# Mosfets.net
KiCad netlist of a schematic drawn in Altium Designer
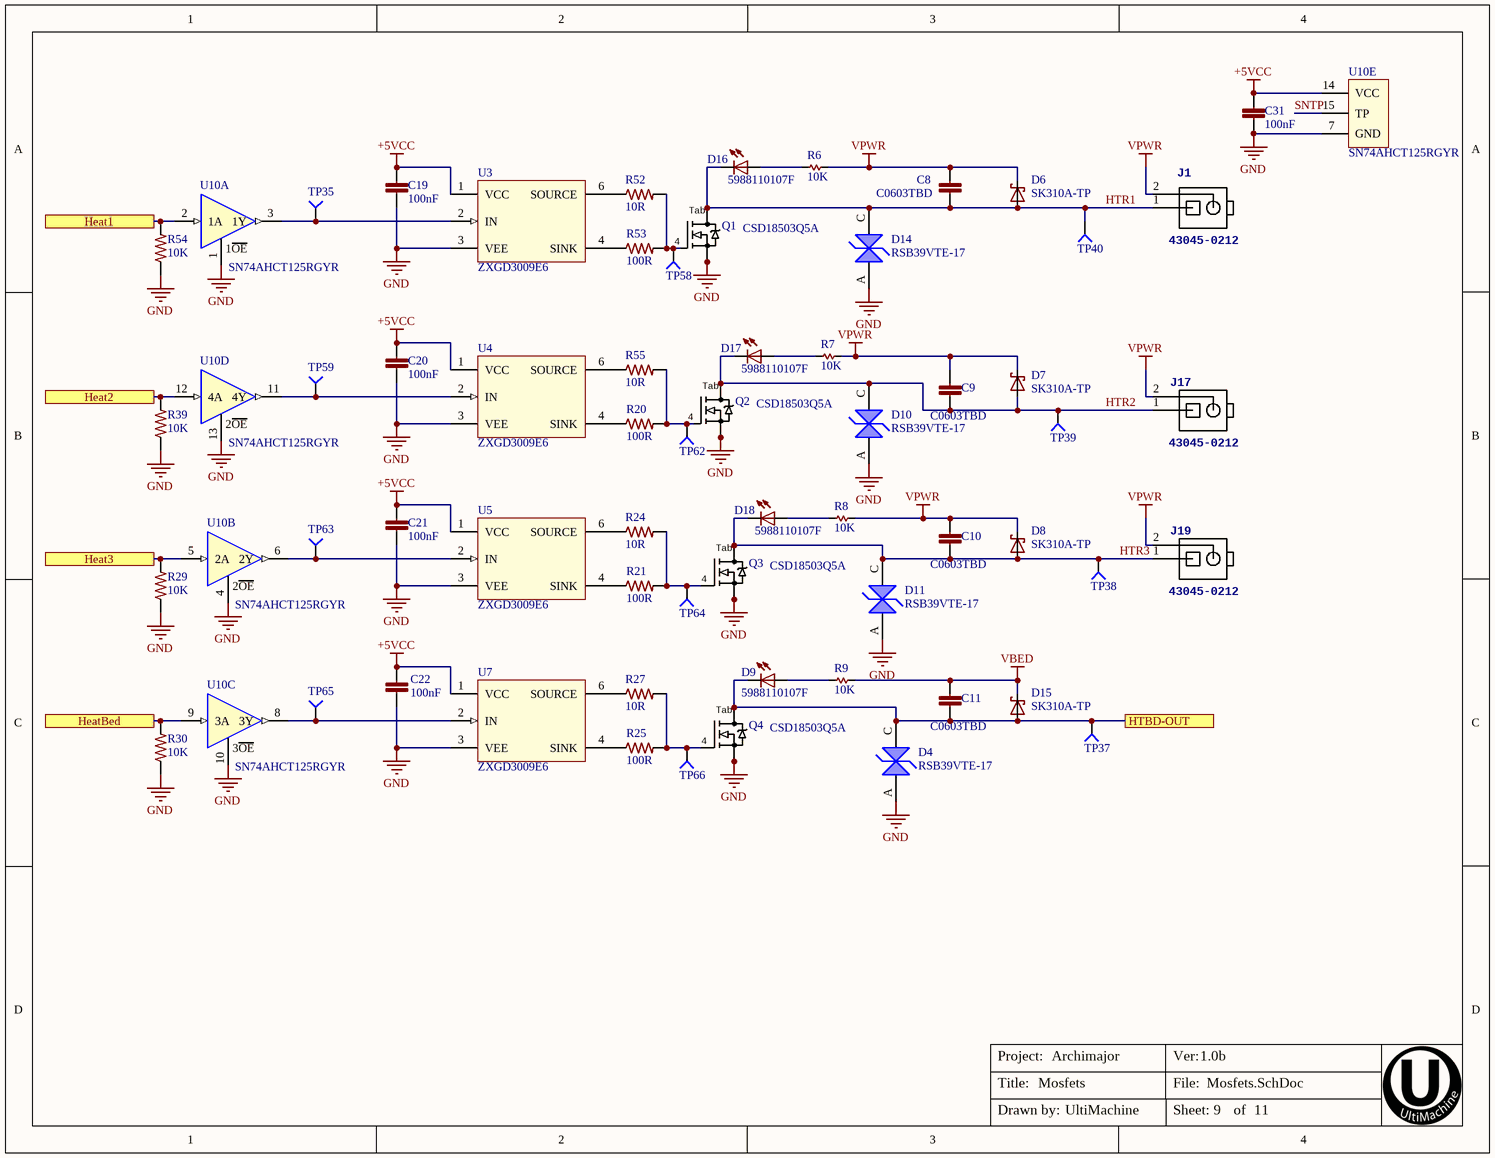
[diagram p0: Mosfets.SchDoc]

(export (version "E")
  (design (tool "Eeschema 10.0.6"))
  (components
    (comp (ref "C8")
      (value "C0603TBD")
      (footprint "C0603")
      (description "Capacitor Non Polarized")
      (fields (field (name "PART") "DNI-C0603TBD"))
      (libsource (lib "3Delight") (part "C0603TBD"))
    )
    (comp (ref "C9")
      (value "C0603TBD")
      (footprint "C0603")
      (description "Capacitor Non Polarized")
      (fields (field (name "PART") "DNI-C0603TBD"))
      (libsource (lib "3Delight") (part "C0603TBD"))
    )
    (comp (ref "C10")
      (value "C0603TBD")
      (footprint "C0603")
      (description "Capacitor Non Polarized")
      (fields (field (name "PART") "DNI-C0603TBD"))
      (libsource (lib "3Delight") (part "C0603TBD"))
    )
    (comp (ref "C11")
      (value "C0603TBD")
      (footprint "C0603")
      (description "Capacitor Non Polarized")
      (fields (field (name "PART") "DNI-C0603TBD"))
      (libsource (lib "3Delight") (part "C0603TBD"))
    )
    (comp (ref "C19")
      (value "100nF")
      (footprint "C0402")
      (description "CAP CER 0402 100nF 16V 10% X7R")
      (fields (field (name "MANUFACTURER") "Murata") (field (name "PART") "GRM155R71C104KA88D"))
      (libsource (lib "3Delight") (part "GRM155R71C104KA88D"))
    )
    (comp (ref "C20")
      (value "100nF")
      (footprint "C0402")
      (description "CAP CER 0402 100nF 16V 10% X7R")
      (fields (field (name "MANUFACTURER") "Murata") (field (name "PART") "GRM155R71C104KA88D"))
      (libsource (lib "3Delight") (part "GRM155R71C104KA88D"))
    )
    (comp (ref "C21")
      (value "100nF")
      (footprint "C0402")
      (description "CAP CER 0402 100nF 16V 10% X7R")
      (fields (field (name "MANUFACTURER") "Murata") (field (name "PART") "GRM155R71C104KA88D"))
      (libsource (lib "3Delight") (part "GRM155R71C104KA88D"))
    )
    (comp (ref "C22")
      (value "100nF")
      (footprint "C0402")
      (description "CAP CER 0402 100nF 16V 10% X7R")
      (fields (field (name "MANUFACTURER") "Murata") (field (name "PART") "GRM155R71C104KA88D"))
      (libsource (lib "") (part "GRM155R71C104KA88D_1"))
    )
    (comp (ref "C31")
      (value "100nF")
      (footprint "C0402")
      (description "CAP CER 0402 100nF 16V 10% X7R")
      (fields (field (name "MANUFACTURER") "Murata") (field (name "PART") "GRM155R71C104KA88D"))
      (libsource (lib "3Delight") (part "GRM155R71C104KA88D"))
    )
    (comp (ref "D4")
      (value "RSB39VTE-17")
      (footprint "SOD323-R")
      (description "DIODE TVS")
      (fields (field (name "MANUFACTURER") "Rohm") (field (name "TOLERANCE") "-NA-"))
      (libsource (lib "3Delight") (part "RSB39VTE-17"))
    )
    (comp (ref "D6")
      (value "SK310A-TP")
      (footprint "SMA-SM")
      (description "DIODE Schottky 3A SMA")
      (fields (field (name "MANUFACTURER") "MCC") (field (name "PART") "SK310A"))
      (libsource (lib "Archim_0.4") (part "SK310A"))
    )
    (comp (ref "D7")
      (value "SK310A-TP")
      (footprint "SMA-SM")
      (description "DIODE Schottky 3A SMA")
      (fields (field (name "MANUFACTURER") "MCC") (field (name "PART") "SK310A"))
      (libsource (lib "Archim_0.4") (part "SK310A"))
    )
    (comp (ref "D8")
      (value "SK310A-TP")
      (footprint "SMA-SM")
      (description "DIODE Schottky 3A SMA")
      (fields (field (name "MANUFACTURER") "MCC") (field (name "PART") "SK310A"))
      (libsource (lib "Archim_0.4") (part "SK310A"))
    )
    (comp (ref "D9")
      (value "Red")
      (footprint "LED2012120")
      (description "LED 0805 Red")
      (fields
        (field (name "MANUFACTURER") "Dialight")
        (field (name "PART") "5988110107F")
        (field (name "TOLERANCE") "-NA-")
      )
      (libsource (lib "3Delight") (part "5988110107F"))
    )
    (comp (ref "D10")
      (value "RSB39VTE-17")
      (footprint "SOD323-R")
      (description "DIODE TVS")
      (fields (field (name "MANUFACTURER") "Rohm") (field (name "TOLERANCE") "-NA-"))
      (libsource (lib "3Delight") (part "RSB39VTE-17"))
    )
    (comp (ref "D11")
      (value "RSB39VTE-17")
      (footprint "SOD323-R")
      (description "DIODE TVS")
      (fields (field (name "MANUFACTURER") "Rohm") (field (name "TOLERANCE") "-NA-"))
      (libsource (lib "3Delight") (part "RSB39VTE-17"))
    )
    (comp (ref "D14")
      (value "RSB39VTE-17")
      (footprint "SOD323-R")
      (description "DIODE TVS")
      (fields (field (name "MANUFACTURER") "Rohm") (field (name "TOLERANCE") "-NA-"))
      (libsource (lib "3Delight") (part "RSB39VTE-17"))
    )
    (comp (ref "D15")
      (value "SK310A-TP")
      (footprint "SMA-SM")
      (description "DIODE Schottky 3A SMA")
      (fields (field (name "MANUFACTURER") "MCC") (field (name "PART") "SK310A"))
      (libsource (lib "Archim_0.4") (part "SK310A"))
    )
    (comp (ref "D16")
      (value "Red")
      (footprint "LED2012120")
      (description "LED 0805 Red")
      (fields
        (field (name "MANUFACTURER") "Dialight")
        (field (name "PART") "5988110107F")
        (field (name "TOLERANCE") "-NA-")
      )
      (libsource (lib "3Delight") (part "5988110107F"))
    )
    (comp (ref "D17")
      (value "Red")
      (footprint "LED2012120")
      (description "LED 0805 Red")
      (fields
        (field (name "MANUFACTURER") "Dialight")
        (field (name "PART") "5988110107F")
        (field (name "TOLERANCE") "-NA-")
      )
      (libsource (lib "3Delight") (part "5988110107F"))
    )
    (comp (ref "D18")
      (value "Red")
      (footprint "LED2012120")
      (description "LED 0805 Red")
      (fields
        (field (name "MANUFACTURER") "Dialight")
        (field (name "PART") "5988110107F")
        (field (name "TOLERANCE") "-NA-")
      )
      (libsource (lib "3Delight") (part "5988110107F"))
    )
    (comp (ref "J1")
      (value "43045-0212")
      (footprint "43045-0212")
      (description "Conn - 3mm Pitch Fixed")
      (fields (field (name "MANUFACTURER") "Molex"))
      (libsource (lib "Connectors") (part "Micro-Fit THT 2pos 3mm"))
    )
    (comp (ref "J17")
      (value "43045-0212")
      (footprint "43045-0212")
      (description "Conn - 3mm Pitch Fixed")
      (fields (field (name "MANUFACTURER") "Molex"))
      (libsource (lib "Connectors") (part "Micro-Fit THT 2pos 3mm"))
    )
    (comp (ref "J19")
      (value "43045-0212")
      (footprint "43045-0212")
      (description "Conn - 3mm Pitch Fixed")
      (fields (field (name "MANUFACTURER") "Molex"))
      (libsource (lib "Connectors") (part "Micro-Fit THT 2pos 3mm"))
    )
    (comp (ref "Q1")
      (value "CSD18503Q5A")
      (footprint "SOT669_Universal")
      (description "MOSFET N-CH 40V 100A 8VSON")
      (fields (field (name "MANUFACTURER") "TI"))
      (libsource (lib "Transistors") (part "CSD18503Q5A"))
    )
    (comp (ref "Q2")
      (value "CSD18503Q5A")
      (footprint "SOT669_Universal")
      (description "MOSFET N-CH 40V 100A 8VSON")
      (fields (field (name "MANUFACTURER") "TI"))
      (libsource (lib "Transistors") (part "CSD18503Q5A"))
    )
    (comp (ref "Q3")
      (value "CSD18503Q5A")
      (footprint "SOT669_Universal")
      (description "MOSFET N-CH 40V 100A 8VSON")
      (fields (field (name "MANUFACTURER") "TI"))
      (libsource (lib "Transistors") (part "CSD18503Q5A"))
    )
    (comp (ref "Q4")
      (value "CSD18503Q5A")
      (footprint "SOT669_Universal")
      (description "MOSFET N-CH 40V 100A 8VSON")
      (fields (field (name "MANUFACTURER") "TI"))
      (libsource (lib "Transistors") (part "CSD18503Q5A"))
    )
    (comp (ref "R6")
      (value "10K")
      (footprint "R0402")
      (description "RES SMD 10K OHM 1% 1/16W 0402")
      (fields (field (name "MANUFACTURER") "Yageo") (field (name "PART") "RC0402FR-0710KP"))
      (libsource (lib "Resistors") (part "10k 1% 0402"))
    )
    (comp (ref "R7")
      (value "10K")
      (footprint "R0402")
      (description "RES SMD 10K OHM 1% 1/16W 0402")
      (fields (field (name "MANUFACTURER") "Yageo") (field (name "PART") "RC0402FR-0710KP"))
      (libsource (lib "Resistors") (part "10k 1% 0402"))
    )
    (comp (ref "R8")
      (value "10K")
      (footprint "R0402")
      (description "RES SMD 10K OHM 1% 1/16W 0402")
      (fields (field (name "MANUFACTURER") "Yageo") (field (name "PART") "RC0402FR-0710KP"))
      (libsource (lib "Resistors") (part "10k 1% 0402"))
    )
    (comp (ref "R9")
      (value "10K")
      (footprint "R0402")
      (description "RES SMD 10K OHM 1% 1/16W 0402")
      (fields (field (name "MANUFACTURER") "Yageo") (field (name "PART") "RC0402FR-0710KP"))
      (libsource (lib "Resistors") (part "10k 1% 0402"))
    )
    (comp (ref "R20")
      (value "100R")
      (footprint "R0402")
      (description "RES SMD 100 OHM 1% 1/16W 0402")
      (fields (field (name "MANUFACTURER") "Yageo") (field (name "PART") "RC0402FR-07100RL"))
      (libsource (lib "Archim") (part "RES 100R 0402 1%"))
    )
    (comp (ref "R21")
      (value "100R")
      (footprint "R0402")
      (description "RES SMD 100 OHM 1% 1/16W 0402")
      (fields (field (name "MANUFACTURER") "Yageo") (field (name "PART") "RC0402FR-07100RL"))
      (libsource (lib "Archim") (part "RES 100R 0402 1%"))
    )
    (comp (ref "R24")
      (value "10R")
      (footprint "R0402")
      (description "RES SMD 10 OHM 1% 1/16W 0402")
      (fields (field (name "MANUFACTURER") "Yageo") (field (name "PART") "RC0402FR-0710RL"))
      (libsource (lib "3Delight") (part "RC0402FR-0710RL"))
    )
    (comp (ref "R25")
      (value "100R")
      (footprint "R0402")
      (description "RES SMD 100 OHM 1% 1/16W 0402")
      (fields (field (name "MANUFACTURER") "Yageo") (field (name "PART") "RC0402FR-07100RL"))
      (libsource (lib "Archim") (part "RES 100R 0402 1%"))
    )
    (comp (ref "R27")
      (value "10R")
      (footprint "R0402")
      (description "RES SMD 10 OHM 1% 1/16W 0402")
      (fields (field (name "MANUFACTURER") "Yageo") (field (name "PART") "RC0402FR-0710RL"))
      (libsource (lib "3Delight") (part "RC0402FR-0710RL"))
    )
    (comp (ref "R29")
      (value "10K")
      (footprint "R0402")
      (description "RES SMD 10K OHM 1% 1/16W 0402")
      (fields (field (name "MANUFACTURER") "Yageo") (field (name "PART") "RC0402FR-0710KP"))
      (libsource (lib "3Delight") (part "RC0402FR-0710KP"))
    )
    (comp (ref "R30")
      (value "10K")
      (footprint "R0402")
      (description "RES SMD 10K OHM 1% 1/16W 0402")
      (fields (field (name "MANUFACTURER") "Yageo") (field (name "PART") "RC0402FR-0710KP"))
      (libsource (lib "3Delight") (part "RC0402FR-0710KP"))
    )
    (comp (ref "R39")
      (value "10K")
      (footprint "R0402")
      (description "RES SMD 10K OHM 1% 1/16W 0402")
      (fields (field (name "MANUFACTURER") "Yageo") (field (name "PART") "RC0402FR-0710KP"))
      (libsource (lib "3Delight") (part "RC0402FR-0710KP"))
    )
    (comp (ref "R52")
      (value "10R")
      (footprint "R0402")
      (description "RES SMD 10 OHM 1% 1/16W 0402")
      (fields (field (name "MANUFACTURER") "Yageo") (field (name "PART") "RC0402FR-0710RL"))
      (libsource (lib "3Delight") (part "RC0402FR-0710RL"))
    )
    (comp (ref "R53")
      (value "100R")
      (footprint "R0402")
      (description "RES SMD 100 OHM 1% 1/16W 0402")
      (fields (field (name "MANUFACTURER") "Yageo") (field (name "PART") "RC0402FR-07100RL"))
      (libsource (lib "Archim") (part "RES 100R 0402 1%"))
    )
    (comp (ref "R54")
      (value "10K")
      (footprint "R0402")
      (description "RES SMD 10K OHM 1% 1/16W 0402")
      (fields (field (name "MANUFACTURER") "Yageo") (field (name "PART") "RC0402FR-0710KP"))
      (libsource (lib "3Delight") (part "RC0402FR-0710KP"))
    )
    (comp (ref "R55")
      (value "10R")
      (footprint "R0402")
      (description "RES SMD 10 OHM 1% 1/16W 0402")
      (fields (field (name "MANUFACTURER") "Yageo") (field (name "PART") "RC0402FR-0710RL"))
      (libsource (lib "3Delight") (part "RC0402FR-0710RL"))
    )
    (comp (ref "TP35")
      (value "TP4")
      (footprint "TP-2")
      (description "Socket")
      (fields (field (name "PART") "NOTAPART-Testpoint"))
      (libsource (lib "Archim") (part "Socket"))
    )
    (comp (ref "TP37")
      (value "TP4")
      (footprint "TP-2")
      (description "Socket")
      (fields (field (name "PART") "NOTAPART-Testpoint"))
      (libsource (lib "Archim") (part "Socket"))
    )
    (comp (ref "TP38")
      (value "TP4")
      (footprint "TP-2")
      (description "Socket")
      (fields (field (name "PART") "NOTAPART-Testpoint"))
      (libsource (lib "Archim") (part "Socket"))
    )
    (comp (ref "TP39")
      (value "TP4")
      (footprint "TP-2")
      (description "Socket")
      (fields (field (name "PART") "NOTAPART-Testpoint"))
      (libsource (lib "Archim") (part "Socket"))
    )
    (comp (ref "TP40")
      (value "TP4")
      (footprint "TP-2")
      (description "Socket")
      (fields (field (name "PART") "NOTAPART-Testpoint"))
      (libsource (lib "Archim") (part "Socket"))
    )
    (comp (ref "TP58")
      (value "TP4")
      (footprint "TP-2")
      (description "Socket")
      (fields (field (name "PART") "NOTAPART-Testpoint"))
      (libsource (lib "Archim") (part "Socket"))
    )
    (comp (ref "TP59")
      (value "TP4")
      (footprint "TP-2")
      (description "Socket")
      (fields (field (name "PART") "NOTAPART-Testpoint"))
      (libsource (lib "Archim") (part "Socket"))
    )
    (comp (ref "TP62")
      (value "TP4")
      (footprint "TP-2")
      (description "Socket")
      (fields (field (name "PART") "NOTAPART-Testpoint"))
      (libsource (lib "Archim") (part "Socket"))
    )
    (comp (ref "TP63")
      (value "TP4")
      (footprint "TP-2")
      (description "Socket")
      (fields (field (name "PART") "NOTAPART-Testpoint"))
      (libsource (lib "Archim") (part "Socket"))
    )
    (comp (ref "TP64")
      (value "TP4")
      (footprint "TP-2")
      (description "Socket")
      (fields (field (name "PART") "NOTAPART-Testpoint"))
      (libsource (lib "Archim") (part "Socket"))
    )
    (comp (ref "TP65")
      (value "TP4")
      (footprint "TP-2")
      (description "Socket")
      (fields (field (name "PART") "NOTAPART-Testpoint"))
      (libsource (lib "Archim") (part "Socket"))
    )
    (comp (ref "TP66")
      (value "TP4")
      (footprint "TP-2")
      (description "Socket")
      (fields (field (name "PART") "NOTAPART-Testpoint"))
      (libsource (lib "Archim") (part "Socket"))
    )
    (comp (ref "U3")
      (value "ZXGD3009E6")
      (footprint "SOT26P285X140-6L")
      (description "MOSFET DRVR 3A 1-OUT High Speed Non-Inv6-Pin SOT-26 T/R")
      (fields (field (name "MANUFACTURER") "Diodes Incorporated") (field (name "PART") "ZXGD3009E6TA"))
      (libsource (lib "3Delight") (part "ZXGD3009E6"))
    )
    (comp (ref "U4")
      (value "ZXGD3009E6")
      (footprint "SOT26P285X140-6L")
      (description "MOSFET DRVR 3A 1-OUT High Speed Non-Inv6-Pin SOT-26 T/R")
      (fields (field (name "MANUFACTURER") "Diodes Incorporated") (field (name "PART") "ZXGD3009E6TA"))
      (libsource (lib "3Delight") (part "ZXGD3009E6"))
    )
    (comp (ref "U5")
      (value "ZXGD3009E6")
      (footprint "SOT26P285X140-6L")
      (description "MOSFET DRVR 3A 1-OUT High Speed Non-Inv6-Pin SOT-26 T/R")
      (fields (field (name "MANUFACTURER") "Diodes Incorporated") (field (name "PART") "ZXGD3009E6TA"))
      (libsource (lib "3Delight") (part "ZXGD3009E6"))
    )
    (comp (ref "U7")
      (value "ZXGD3009E6")
      (footprint "SOT26P285X140-6L")
      (description "MOSFET DRVR 3A 1-OUT High Speed Non-Inv6-Pin SOT-26 T/R")
      (fields (field (name "MANUFACTURER") "Diodes Incorporated") (field (name "PART") "ZXGD3009E6TA"))
      (libsource (lib "3Delight") (part "ZXGD3009E6"))
    )
    (comp (ref "U10")
      (value "SN74AHCT125RGYR")
      (footprint "QFN50P350X350X100_RGY_S-PVQFN-N14")
      (description "Quadruple Bus Buffer Gates With 3-State Outputs 14-VQFN -40 to 125")
      (fields (field (name "MANUFACTURER") "Texas Instruments") (field (name "TOLERANCE") "-NA-"))
      (libsource (lib "3Delight") (part "SN74AHCT125"))
    )
  )
  (nets
    (net (code "1") (name "+5VCC") (class "Default")
      (node (ref "C19") (pin "2") (pinfunction "2_2") (pintype "passive"))
      (node (ref "C20") (pin "2") (pinfunction "2_2") (pintype "passive"))
      (node (ref "C21") (pin "2") (pinfunction "2_2") (pintype "passive"))
      (node (ref "C22") (pin "1") (pinfunction "1_1") (pintype "passive"))
      (node (ref "C31") (pin "2") (pinfunction "2_2") (pintype "passive"))
      (node (ref "U10") (pin "14") (pinfunction "VCC_14") (pintype "power_in"))
      (node (ref "U3") (pin "1") (pinfunction "VCC_1") (pintype "power_in"))
      (node (ref "U4") (pin "1") (pinfunction "VCC_1") (pintype "power_in"))
      (node (ref "U5") (pin "1") (pinfunction "VCC_1") (pintype "power_in"))
      (node (ref "U7") (pin "1") (pinfunction "VCC_1") (pintype "power_in"))
    )
    (net (code "2") (name "/HTBD-OUT") (class "Default")
      (node (ref "C11") (pin "2") (pinfunction "2_2") (pintype "passive"))
      (node (ref "D15") (pin "A") (pinfunction "A_A") (pintype "passive"))
      (node (ref "D4") (pin "C") (pinfunction "C_C") (pintype "power_in"))
      (node (ref "D9") (pin "C") (pinfunction "C_C") (pintype "passive"))
      (node (ref "Q4") (pin "TAB") (pinfunction "D_TAB") (pintype "passive"))
      (node (ref "TP37") (pin "1") (pinfunction "1_1") (pintype "passive"))
    )
    (net (code "3") (name "/HTR1") (class "Default")
      (node (ref "C8") (pin "2") (pinfunction "2_2") (pintype "passive"))
      (node (ref "D14") (pin "C") (pinfunction "C_C") (pintype "power_in"))
      (node (ref "D16") (pin "C") (pinfunction "C_C") (pintype "passive"))
      (node (ref "D6") (pin "A") (pinfunction "A_A") (pintype "passive"))
      (node (ref "J1") (pin "1") (pinfunction "4_1") (pintype "power_in"))
      (node (ref "Q1") (pin "TAB") (pinfunction "D_TAB") (pintype "passive"))
      (node (ref "TP40") (pin "1") (pinfunction "1_1") (pintype "passive"))
    )
    (net (code "4") (name "/HTR2") (class "Default")
      (node (ref "C9") (pin "2") (pinfunction "2_2") (pintype "passive"))
      (node (ref "D10") (pin "C") (pinfunction "C_C") (pintype "power_in"))
      (node (ref "D17") (pin "C") (pinfunction "C_C") (pintype "passive"))
      (node (ref "D7") (pin "A") (pinfunction "A_A") (pintype "passive"))
      (node (ref "J17") (pin "1") (pinfunction "4_1") (pintype "power_in"))
      (node (ref "Q2") (pin "TAB") (pinfunction "D_TAB") (pintype "passive"))
      (node (ref "TP39") (pin "1") (pinfunction "1_1") (pintype "passive"))
    )
    (net (code "5") (name "/HTR3") (class "Default")
      (node (ref "C10") (pin "2") (pinfunction "2_2") (pintype "passive"))
      (node (ref "D11") (pin "C") (pinfunction "C_C") (pintype "power_in"))
      (node (ref "D18") (pin "C") (pinfunction "C_C") (pintype "passive"))
      (node (ref "D8") (pin "A") (pinfunction "A_A") (pintype "passive"))
      (node (ref "J19") (pin "1") (pinfunction "4_1") (pintype "power_in"))
      (node (ref "Q3") (pin "TAB") (pinfunction "D_TAB") (pintype "passive"))
      (node (ref "TP38") (pin "1") (pinfunction "1_1") (pintype "passive"))
    )
    (net (code "6") (name "/Heat1") (class "Default")
      (node (ref "R54") (pin "2") (pinfunction "2_2") (pintype "passive"))
      (node (ref "U10") (pin "2") (pinfunction "1A_2") (pintype "input"))
    )
    (net (code "7") (name "/Heat2") (class "Default")
      (node (ref "R39") (pin "2") (pinfunction "2_2") (pintype "passive"))
      (node (ref "U10") (pin "12") (pinfunction "4A_12") (pintype "input"))
    )
    (net (code "8") (name "/Heat3") (class "Default")
      (node (ref "R29") (pin "2") (pinfunction "2_2") (pintype "passive"))
      (node (ref "U10") (pin "5") (pinfunction "2A_5") (pintype "input"))
    )
    (net (code "9") (name "/HeatBed") (class "Default")
      (node (ref "R30") (pin "2") (pinfunction "2_2") (pintype "passive"))
      (node (ref "U10") (pin "9") (pinfunction "3A_9") (pintype "input"))
    )
    (net (code "10") (name "/SNTP") (class "Default")
      (node (ref "U10") (pin "15") (pinfunction "TP_15") (pintype "power_in"))
    )
    (net (code "11") (name "GND") (class "Default")
      (node (ref "C19") (pin "1") (pinfunction "1_1") (pintype "passive"))
      (node (ref "C20") (pin "1") (pinfunction "1_1") (pintype "passive"))
      (node (ref "C21") (pin "1") (pinfunction "1_1") (pintype "passive"))
      (node (ref "C22") (pin "2") (pinfunction "2_2") (pintype "passive"))
      (node (ref "C31") (pin "1") (pinfunction "1_1") (pintype "passive"))
      (node (ref "D10") (pin "A") (pinfunction "A_A") (pintype "power_in"))
      (node (ref "D11") (pin "A") (pinfunction "A_A") (pintype "power_in"))
      (node (ref "D14") (pin "A") (pinfunction "A_A") (pintype "power_in"))
      (node (ref "D4") (pin "A") (pinfunction "A_A") (pintype "power_in"))
      (node (ref "Q1") (pin "1") (pinfunction "S_1") (pintype "passive"))
      (node (ref "Q1") (pin "2") (pinfunction "S_2") (pintype "passive"))
      (node (ref "Q1") (pin "3") (pinfunction "S_3") (pintype "passive"))
      (node (ref "Q2") (pin "1") (pinfunction "S_1") (pintype "passive"))
      (node (ref "Q2") (pin "2") (pinfunction "S_2") (pintype "passive"))
      (node (ref "Q2") (pin "3") (pinfunction "S_3") (pintype "passive"))
      (node (ref "Q3") (pin "1") (pinfunction "S_1") (pintype "passive"))
      (node (ref "Q3") (pin "2") (pinfunction "S_2") (pintype "passive"))
      (node (ref "Q3") (pin "3") (pinfunction "S_3") (pintype "passive"))
      (node (ref "Q4") (pin "1") (pinfunction "S_1") (pintype "passive"))
      (node (ref "Q4") (pin "2") (pinfunction "S_2") (pintype "passive"))
      (node (ref "Q4") (pin "3") (pinfunction "S_3") (pintype "passive"))
      (node (ref "R29") (pin "1") (pinfunction "1_1") (pintype "passive"))
      (node (ref "R30") (pin "1") (pinfunction "1_1") (pintype "passive"))
      (node (ref "R39") (pin "1") (pinfunction "1_1") (pintype "passive"))
      (node (ref "R54") (pin "1") (pinfunction "1_1") (pintype "passive"))
      (node (ref "U10") (pin "1") (pinfunction "1OE_1") (pintype "power_in"))
      (node (ref "U10") (pin "10") (pinfunction "3OE_10") (pintype "power_in"))
      (node (ref "U10") (pin "13") (pinfunction "4OE_13") (pintype "power_in"))
      (node (ref "U10") (pin "4") (pinfunction "2OE_4") (pintype "power_in"))
      (node (ref "U10") (pin "7") (pinfunction "GND_7") (pintype "power_in"))
      (node (ref "U3") (pin "3") (pinfunction "VEE_3") (pintype "power_in"))
      (node (ref "U4") (pin "3") (pinfunction "VEE_3") (pintype "power_in"))
      (node (ref "U5") (pin "3") (pinfunction "VEE_3") (pintype "power_in"))
      (node (ref "U7") (pin "3") (pinfunction "VEE_3") (pintype "power_in"))
    )
    (net (code "12") (name "Net-(D9-PadA)") (class "Default")
      (node (ref "D9") (pin "A") (pinfunction "A_A") (pintype "passive"))
      (node (ref "R9") (pin "1") (pinfunction "1_1") (pintype "passive"))
    )
    (net (code "13") (name "Net-(D16-PadA)") (class "Default")
      (node (ref "D16") (pin "A") (pinfunction "A_A") (pintype "passive"))
      (node (ref "R6") (pin "1") (pinfunction "1_1") (pintype "passive"))
    )
    (net (code "14") (name "Net-(D17-PadA)") (class "Default")
      (node (ref "D17") (pin "A") (pinfunction "A_A") (pintype "passive"))
      (node (ref "R7") (pin "1") (pinfunction "1_1") (pintype "passive"))
    )
    (net (code "15") (name "Net-(D18-PadA)") (class "Default")
      (node (ref "D18") (pin "A") (pinfunction "A_A") (pintype "passive"))
      (node (ref "R8") (pin "1") (pinfunction "1_1") (pintype "passive"))
    )
    (net (code "16") (name "Net-(Q1-G)") (class "Default")
      (node (ref "Q1") (pin "4") (pinfunction "G_4") (pintype "passive"))
      (node (ref "R52") (pin "2") (pinfunction "2_2") (pintype "passive"))
      (node (ref "R53") (pin "2") (pinfunction "2_2") (pintype "passive"))
      (node (ref "TP58") (pin "1") (pinfunction "1_1") (pintype "passive"))
    )
    (net (code "17") (name "Net-(Q2-G)") (class "Default")
      (node (ref "Q2") (pin "4") (pinfunction "G_4") (pintype "passive"))
      (node (ref "R20") (pin "2") (pinfunction "2_2") (pintype "passive"))
      (node (ref "R55") (pin "2") (pinfunction "2_2") (pintype "passive"))
      (node (ref "TP62") (pin "1") (pinfunction "1_1") (pintype "passive"))
    )
    (net (code "18") (name "Net-(Q3-G)") (class "Default")
      (node (ref "Q3") (pin "4") (pinfunction "G_4") (pintype "passive"))
      (node (ref "R21") (pin "2") (pinfunction "2_2") (pintype "passive"))
      (node (ref "R24") (pin "2") (pinfunction "2_2") (pintype "passive"))
      (node (ref "TP64") (pin "1") (pinfunction "1_1") (pintype "passive"))
    )
    (net (code "19") (name "Net-(Q4-G)") (class "Default")
      (node (ref "Q4") (pin "4") (pinfunction "G_4") (pintype "passive"))
      (node (ref "R25") (pin "2") (pinfunction "2_2") (pintype "passive"))
      (node (ref "R27") (pin "2") (pinfunction "2_2") (pintype "passive"))
      (node (ref "TP66") (pin "1") (pinfunction "1_1") (pintype "passive"))
    )
    (net (code "20") (name "Net-(U3-SINK)") (class "Default")
      (node (ref "R53") (pin "1") (pinfunction "1_1") (pintype "passive"))
      (node (ref "U3") (pin "4") (pinfunction "SINK_4") (pintype "power_in"))
    )
    (net (code "21") (name "Net-(U3-SOURCE)") (class "Default")
      (node (ref "R52") (pin "1") (pinfunction "1_1") (pintype "passive"))
      (node (ref "U3") (pin "6") (pinfunction "SOURCE_6") (pintype "power_in"))
    )
    (net (code "22") (name "Net-(U4-SINK)") (class "Default")
      (node (ref "R20") (pin "1") (pinfunction "1_1") (pintype "passive"))
      (node (ref "U4") (pin "4") (pinfunction "SINK_4") (pintype "power_in"))
    )
    (net (code "23") (name "Net-(U4-SOURCE)") (class "Default")
      (node (ref "R55") (pin "1") (pinfunction "1_1") (pintype "passive"))
      (node (ref "U4") (pin "6") (pinfunction "SOURCE_6") (pintype "power_in"))
    )
    (net (code "24") (name "Net-(U5-SINK)") (class "Default")
      (node (ref "R21") (pin "1") (pinfunction "1_1") (pintype "passive"))
      (node (ref "U5") (pin "4") (pinfunction "SINK_4") (pintype "power_in"))
    )
    (net (code "25") (name "Net-(U5-SOURCE)") (class "Default")
      (node (ref "R24") (pin "1") (pinfunction "1_1") (pintype "passive"))
      (node (ref "U5") (pin "6") (pinfunction "SOURCE_6") (pintype "power_in"))
    )
    (net (code "26") (name "Net-(U7-SINK)") (class "Default")
      (node (ref "R25") (pin "1") (pinfunction "1_1") (pintype "passive"))
      (node (ref "U7") (pin "4") (pinfunction "SINK_4") (pintype "power_in"))
    )
    (net (code "27") (name "Net-(U7-SOURCE)") (class "Default")
      (node (ref "R27") (pin "1") (pinfunction "1_1") (pintype "passive"))
      (node (ref "U7") (pin "6") (pinfunction "SOURCE_6") (pintype "power_in"))
    )
    (net (code "28") (name "Net-(U10A-1Y)") (class "Default")
      (node (ref "TP35") (pin "1") (pinfunction "1_1") (pintype "passive"))
      (node (ref "U10") (pin "3") (pinfunction "1Y_3") (pintype "output"))
      (node (ref "U3") (pin "2") (pinfunction "IN_2") (pintype "input"))
    )
    (net (code "29") (name "Net-(U10B-2Y)") (class "Default")
      (node (ref "TP63") (pin "1") (pinfunction "1_1") (pintype "passive"))
      (node (ref "U10") (pin "6") (pinfunction "2Y_6") (pintype "output"))
      (node (ref "U5") (pin "2") (pinfunction "IN_2") (pintype "input"))
    )
    (net (code "30") (name "Net-(U10C-3Y)") (class "Default")
      (node (ref "TP65") (pin "1") (pinfunction "1_1") (pintype "passive"))
      (node (ref "U10") (pin "8") (pinfunction "3Y_8") (pintype "output"))
      (node (ref "U7") (pin "2") (pinfunction "IN_2") (pintype "input"))
    )
    (net (code "31") (name "Net-(U10D-4Y)") (class "Default")
      (node (ref "TP59") (pin "1") (pinfunction "1_1") (pintype "passive"))
      (node (ref "U10") (pin "11") (pinfunction "4Y_11") (pintype "output"))
      (node (ref "U4") (pin "2") (pinfunction "IN_2") (pintype "input"))
    )
    (net (code "32") (name "VBED") (class "Default")
      (node (ref "C11") (pin "1") (pinfunction "1_1") (pintype "passive"))
      (node (ref "D15") (pin "C") (pinfunction "C_C") (pintype "passive"))
      (node (ref "R9") (pin "2") (pinfunction "2_2") (pintype "passive"))
    )
    (net (code "33") (name "VPWR") (class "Default")
      (node (ref "C10") (pin "1") (pinfunction "1_1") (pintype "passive"))
      (node (ref "C8") (pin "1") (pinfunction "1_1") (pintype "passive"))
      (node (ref "C9") (pin "1") (pinfunction "1_1") (pintype "passive"))
      (node (ref "D6") (pin "C") (pinfunction "C_C") (pintype "passive"))
      (node (ref "D7") (pin "C") (pinfunction "C_C") (pintype "passive"))
      (node (ref "D8") (pin "C") (pinfunction "C_C") (pintype "passive"))
      (node (ref "J1") (pin "2") (pinfunction "2_2") (pintype "power_in"))
      (node (ref "J17") (pin "2") (pinfunction "2_2") (pintype "power_in"))
      (node (ref "J19") (pin "2") (pinfunction "2_2") (pintype "power_in"))
      (node (ref "R6") (pin "2") (pinfunction "2_2") (pintype "passive"))
      (node (ref "R7") (pin "2") (pinfunction "2_2") (pintype "passive"))
      (node (ref "R8") (pin "2") (pinfunction "2_2") (pintype "passive"))
    )
  )
)
